# AIO_Sheet1.net
KiCad netlist of a schematic drawn in Altium Designer
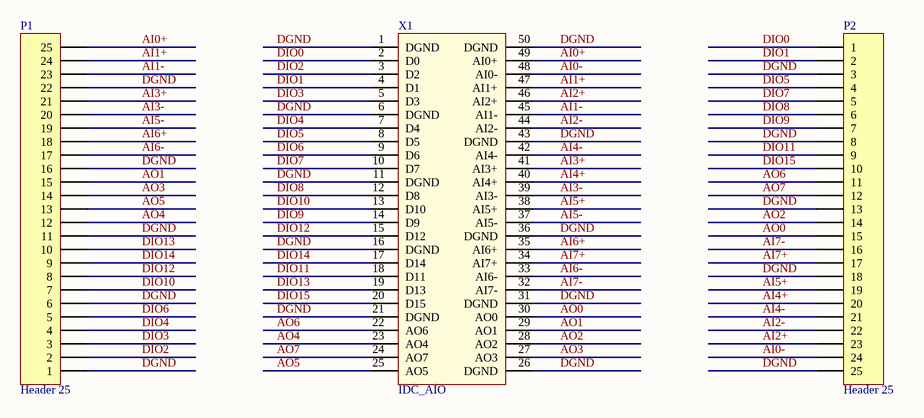
[diagram p0: AIO_Sheet1.SchDoc]

(export (version "E")
  (design (tool "Eeschema 10.0.6"))
  (components
    (comp (ref "P1")
      (value "Header 25")
      (footprint "HDR1X25")
      (description "Header, 25-Pin")
      (fields (field (name "PUBLISHER") "Altium Limited"))
      (libsource (lib "Miscellaneous Connectors") (part "Header 25"))
    )
    (comp (ref "P2")
      (value "Header 25")
      (footprint "HDR1X25")
      (description "Header, 25-Pin")
      (fields (field (name "PUBLISHER") "Altium Limited"))
      (libsource (lib "") (part "Header 25_1"))
    )
    (comp (ref "X1") (value "IDC_AIO") (footprint "IDC_AIO") (libsource (lib "VPL") (part "IDC_AIO")))
  )
  (nets
    (net (code "1") (name "/AI0+") (class "Default")
      (node (ref "P1") (pin "25") (pinfunction "25_25") (pintype "passive"))
      (node (ref "X1") (pin "49") (pinfunction "AI0+_49") (pintype "passive"))
    )
    (net (code "2") (name "/AI0-") (class "Default")
      (node (ref "P2") (pin "24") (pinfunction "24_24") (pintype "passive"))
      (node (ref "X1") (pin "48") (pinfunction "AI0-_48") (pintype "passive"))
    )
    (net (code "3") (name "/AI1+") (class "Default")
      (node (ref "P1") (pin "24") (pinfunction "24_24") (pintype "passive"))
      (node (ref "X1") (pin "47") (pinfunction "AI1+_47") (pintype "passive"))
    )
    (net (code "4") (name "/AI1-") (class "Default")
      (node (ref "P1") (pin "23") (pinfunction "23_23") (pintype "passive"))
      (node (ref "X1") (pin "45") (pinfunction "AI1-_45") (pintype "passive"))
    )
    (net (code "5") (name "/AI2+") (class "Default")
      (node (ref "P2") (pin "23") (pinfunction "23_23") (pintype "passive"))
      (node (ref "X1") (pin "46") (pinfunction "AI2+_46") (pintype "passive"))
    )
    (net (code "6") (name "/AI2-") (class "Default")
      (node (ref "P2") (pin "22") (pinfunction "22_22") (pintype "passive"))
      (node (ref "X1") (pin "44") (pinfunction "AI2-_44") (pintype "passive"))
    )
    (net (code "7") (name "/AI3+") (class "Default")
      (node (ref "P1") (pin "21") (pinfunction "21_21") (pintype "passive"))
      (node (ref "X1") (pin "41") (pinfunction "AI3+_41") (pintype "passive"))
    )
    (net (code "8") (name "/AI3-") (class "Default")
      (node (ref "P1") (pin "20") (pinfunction "20_20") (pintype "passive"))
      (node (ref "X1") (pin "39") (pinfunction "AI3-_39") (pintype "passive"))
    )
    (net (code "9") (name "/AI4+") (class "Default")
      (node (ref "P2") (pin "20") (pinfunction "20_20") (pintype "passive"))
      (node (ref "X1") (pin "40") (pinfunction "AI4+_40") (pintype "passive"))
    )
    (net (code "10") (name "/AI4-") (class "Default")
      (node (ref "P2") (pin "21") (pinfunction "21_21") (pintype "passive"))
      (node (ref "X1") (pin "42") (pinfunction "AI4-_42") (pintype "passive"))
    )
    (net (code "11") (name "/AI5+") (class "Default")
      (node (ref "P2") (pin "19") (pinfunction "19_19") (pintype "passive"))
      (node (ref "X1") (pin "38") (pinfunction "AI5+_38") (pintype "passive"))
    )
    (net (code "12") (name "/AI5-") (class "Default")
      (node (ref "P1") (pin "19") (pinfunction "19_19") (pintype "passive"))
      (node (ref "X1") (pin "37") (pinfunction "AI5-_37") (pintype "passive"))
    )
    (net (code "13") (name "/AI6+") (class "Default")
      (node (ref "P1") (pin "18") (pinfunction "18_18") (pintype "passive"))
      (node (ref "X1") (pin "35") (pinfunction "AI6+_35") (pintype "passive"))
    )
    (net (code "14") (name "/AI6-") (class "Default")
      (node (ref "P1") (pin "17") (pinfunction "17_17") (pintype "passive"))
      (node (ref "X1") (pin "33") (pinfunction "AI6-_33") (pintype "passive"))
    )
    (net (code "15") (name "/AI7+") (class "Default")
      (node (ref "P2") (pin "17") (pinfunction "17_17") (pintype "passive"))
      (node (ref "X1") (pin "34") (pinfunction "AI7+_34") (pintype "passive"))
    )
    (net (code "16") (name "/AI7-") (class "Default")
      (node (ref "P2") (pin "16") (pinfunction "16_16") (pintype "passive"))
      (node (ref "X1") (pin "32") (pinfunction "AI7-_32") (pintype "passive"))
    )
    (net (code "17") (name "/AO0") (class "Default")
      (node (ref "P2") (pin "15") (pinfunction "15_15") (pintype "passive"))
      (node (ref "X1") (pin "30") (pinfunction "AO0_30") (pintype "passive"))
    )
    (net (code "18") (name "/AO1") (class "Default")
      (node (ref "P1") (pin "15") (pinfunction "15_15") (pintype "passive"))
      (node (ref "X1") (pin "29") (pinfunction "AO1_29") (pintype "passive"))
    )
    (net (code "19") (name "/AO2") (class "Default")
      (node (ref "P2") (pin "14") (pinfunction "14_14") (pintype "passive"))
      (node (ref "X1") (pin "28") (pinfunction "AO2_28") (pintype "passive"))
    )
    (net (code "20") (name "/AO3") (class "Default")
      (node (ref "P1") (pin "14") (pinfunction "14_14") (pintype "passive"))
      (node (ref "X1") (pin "27") (pinfunction "AO3_27") (pintype "passive"))
    )
    (net (code "21") (name "/AO4") (class "Default")
      (node (ref "P1") (pin "12") (pinfunction "12_12") (pintype "passive"))
      (node (ref "X1") (pin "23") (pinfunction "AO4_23") (pintype "passive"))
    )
    (net (code "22") (name "/AO5") (class "Default")
      (node (ref "P1") (pin "13") (pinfunction "13_13") (pintype "passive"))
      (node (ref "X1") (pin "25") (pinfunction "AO5_25") (pintype "passive"))
    )
    (net (code "23") (name "/AO6") (class "Default")
      (node (ref "P2") (pin "11") (pinfunction "11_11") (pintype "passive"))
      (node (ref "X1") (pin "22") (pinfunction "AO6_22") (pintype "passive"))
    )
    (net (code "24") (name "/AO7") (class "Default")
      (node (ref "P2") (pin "12") (pinfunction "12_12") (pintype "passive"))
      (node (ref "X1") (pin "24") (pinfunction "AO7_24") (pintype "passive"))
    )
    (net (code "25") (name "/DGND") (class "Default")
      (node (ref "P1") (pin "1") (pinfunction "1_1") (pintype "passive"))
      (node (ref "P1") (pin "11") (pinfunction "11_11") (pintype "passive"))
      (node (ref "P1") (pin "16") (pinfunction "16_16") (pintype "passive"))
      (node (ref "P1") (pin "22") (pinfunction "22_22") (pintype "passive"))
      (node (ref "P1") (pin "6") (pinfunction "6_6") (pintype "passive"))
      (node (ref "P2") (pin "13") (pinfunction "13_13") (pintype "passive"))
      (node (ref "P2") (pin "18") (pinfunction "18_18") (pintype "passive"))
      (node (ref "P2") (pin "25") (pinfunction "25_25") (pintype "passive"))
      (node (ref "P2") (pin "3") (pinfunction "3_3") (pintype "passive"))
      (node (ref "P2") (pin "8") (pinfunction "8_8") (pintype "passive"))
      (node (ref "X1") (pin "1") (pinfunction "DGND_1") (pintype "passive"))
      (node (ref "X1") (pin "11") (pinfunction "DGND_11") (pintype "passive"))
      (node (ref "X1") (pin "16") (pinfunction "DGND_16") (pintype "passive"))
      (node (ref "X1") (pin "21") (pinfunction "DGND_21") (pintype "passive"))
      (node (ref "X1") (pin "26") (pinfunction "DGND_26") (pintype "passive"))
      (node (ref "X1") (pin "31") (pinfunction "DGND_31") (pintype "passive"))
      (node (ref "X1") (pin "36") (pinfunction "DGND_36") (pintype "passive"))
      (node (ref "X1") (pin "43") (pinfunction "DGND_43") (pintype "passive"))
      (node (ref "X1") (pin "50") (pinfunction "DGND_50") (pintype "passive"))
      (node (ref "X1") (pin "6") (pinfunction "DGND_6") (pintype "passive"))
    )
    (net (code "26") (name "/DIO0") (class "Default")
      (node (ref "P2") (pin "1") (pinfunction "1_1") (pintype "passive"))
      (node (ref "X1") (pin "2") (pinfunction "D0_2") (pintype "passive"))
    )
    (net (code "27") (name "/DIO1") (class "Default")
      (node (ref "P2") (pin "2") (pinfunction "2_2") (pintype "passive"))
      (node (ref "X1") (pin "4") (pinfunction "D1_4") (pintype "passive"))
    )
    (net (code "28") (name "/DIO2") (class "Default")
      (node (ref "P1") (pin "2") (pinfunction "2_2") (pintype "passive"))
      (node (ref "X1") (pin "3") (pinfunction "D2_3") (pintype "passive"))
    )
    (net (code "29") (name "/DIO3") (class "Default")
      (node (ref "P1") (pin "3") (pinfunction "3_3") (pintype "passive"))
      (node (ref "X1") (pin "5") (pinfunction "D3_5") (pintype "passive"))
    )
    (net (code "30") (name "/DIO4") (class "Default")
      (node (ref "P1") (pin "4") (pinfunction "4_4") (pintype "passive"))
      (node (ref "X1") (pin "7") (pinfunction "D4_7") (pintype "passive"))
    )
    (net (code "31") (name "/DIO5") (class "Default")
      (node (ref "P2") (pin "4") (pinfunction "4_4") (pintype "passive"))
      (node (ref "X1") (pin "8") (pinfunction "D5_8") (pintype "passive"))
    )
    (net (code "32") (name "/DIO6") (class "Default")
      (node (ref "P1") (pin "5") (pinfunction "5_5") (pintype "passive"))
      (node (ref "X1") (pin "9") (pinfunction "D6_9") (pintype "passive"))
    )
    (net (code "33") (name "/DIO7") (class "Default")
      (node (ref "P2") (pin "5") (pinfunction "5_5") (pintype "passive"))
      (node (ref "X1") (pin "10") (pinfunction "D7_10") (pintype "passive"))
    )
    (net (code "34") (name "/DIO8") (class "Default")
      (node (ref "P2") (pin "6") (pinfunction "6_6") (pintype "passive"))
      (node (ref "X1") (pin "12") (pinfunction "D8_12") (pintype "passive"))
    )
    (net (code "35") (name "/DIO9") (class "Default")
      (node (ref "P2") (pin "7") (pinfunction "7_7") (pintype "passive"))
      (node (ref "X1") (pin "14") (pinfunction "D9_14") (pintype "passive"))
    )
    (net (code "36") (name "/DIO10") (class "Default")
      (node (ref "P1") (pin "7") (pinfunction "7_7") (pintype "passive"))
      (node (ref "X1") (pin "13") (pinfunction "D10_13") (pintype "passive"))
    )
    (net (code "37") (name "/DIO11") (class "Default")
      (node (ref "P2") (pin "9") (pinfunction "9_9") (pintype "passive"))
      (node (ref "X1") (pin "18") (pinfunction "D11_18") (pintype "passive"))
    )
    (net (code "38") (name "/DIO12") (class "Default")
      (node (ref "P1") (pin "8") (pinfunction "8_8") (pintype "passive"))
      (node (ref "X1") (pin "15") (pinfunction "D12_15") (pintype "passive"))
    )
    (net (code "39") (name "/DIO13") (class "Default")
      (node (ref "P1") (pin "10") (pinfunction "10_10") (pintype "passive"))
      (node (ref "X1") (pin "19") (pinfunction "D13_19") (pintype "passive"))
    )
    (net (code "40") (name "/DIO14") (class "Default")
      (node (ref "P1") (pin "9") (pinfunction "9_9") (pintype "passive"))
      (node (ref "X1") (pin "17") (pinfunction "D14_17") (pintype "passive"))
    )
    (net (code "41") (name "/DIO15") (class "Default")
      (node (ref "P2") (pin "10") (pinfunction "10_10") (pintype "passive"))
      (node (ref "X1") (pin "20") (pinfunction "D15_20") (pintype "passive"))
    )
  )
)
